# Sheet_X_button.net
KiCad netlist of a schematic drawn in Altium Designer
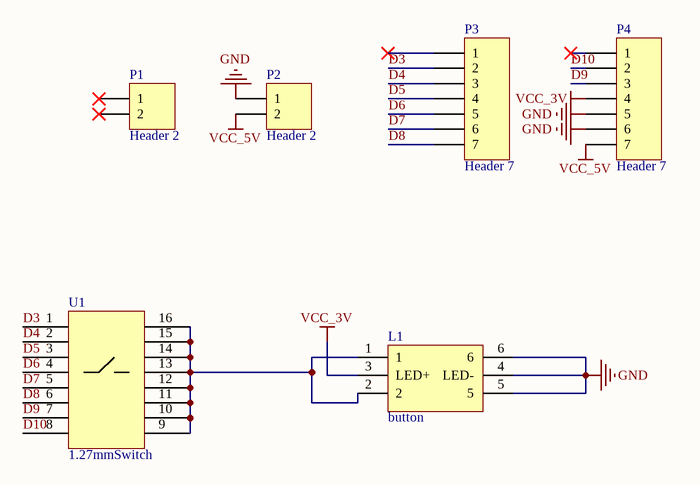
[diagram p0: Sheet_X_button.SchDoc]

(export (version "E")
  (design (tool "Eeschema 10.0.6"))
  (components
    (comp (ref "L1")
      (value "button")
      (footprint "ledbutton")
      (description "蓝色LED按键")
      (libsource (lib "Schlib_OLEDMCU") (part "LEDbutton"))
    )
    (comp (ref "P1")
      (value "Header 2")
      (footprint "HDR1X2")
      (description "Header, 2-Pin")
      (fields (field (name "PUBLISHER") "Altium Limited"))
      (libsource (lib "Miscellaneous Connectors") (part "Header 2"))
    )
    (comp (ref "P2")
      (value "Header 2")
      (footprint "HDR1X2")
      (description "Header, 2-Pin")
      (fields (field (name "PUBLISHER") "Altium Limited"))
      (libsource (lib "Miscellaneous Connectors") (part "Header 2"))
    )
    (comp (ref "P3")
      (value "Header 7")
      (footprint "HDR1X7")
      (description "Header, 7-Pin")
      (fields (field (name "PUBLISHER") "Altium Limited"))
      (libsource (lib "Miscellaneous Connectors") (part "Header 7"))
    )
    (comp (ref "P4")
      (value "Header 7")
      (footprint "HDR1X7")
      (description "Header, 7-Pin")
      (fields (field (name "PUBLISHER") "Altium Limited"))
      (libsource (lib "Miscellaneous Connectors") (part "Header 7"))
    )
    (comp (ref "U1")
      (value "1.27mmSwitch")
      (footprint "NumberSwitch")
      (description "拨码开关")
      (libsource (lib "Schlib_OLEDMCU") (part "NumberSwitch"))
    )
  )
  (nets
    (net (code "1") (name "/D3") (class "Default")
      (node (ref "P3") (pin "2") (pinfunction "2_2") (pintype "passive"))
      (node (ref "U1") (pin "1") (pinfunction "1_1") (pintype "passive"))
    )
    (net (code "2") (name "/D4") (class "Default")
      (node (ref "P3") (pin "3") (pinfunction "3_3") (pintype "passive"))
      (node (ref "U1") (pin "2") (pinfunction "2_2") (pintype "passive"))
    )
    (net (code "3") (name "/D5") (class "Default")
      (node (ref "P3") (pin "4") (pinfunction "4_4") (pintype "passive"))
      (node (ref "U1") (pin "3") (pinfunction "3_3") (pintype "passive"))
    )
    (net (code "4") (name "/D6") (class "Default")
      (node (ref "P3") (pin "5") (pinfunction "5_5") (pintype "passive"))
      (node (ref "U1") (pin "4") (pinfunction "4_4") (pintype "passive"))
    )
    (net (code "5") (name "/D7") (class "Default")
      (node (ref "P3") (pin "6") (pinfunction "6_6") (pintype "passive"))
      (node (ref "U1") (pin "5") (pinfunction "5_5") (pintype "passive"))
    )
    (net (code "6") (name "/D8") (class "Default")
      (node (ref "P3") (pin "7") (pinfunction "7_7") (pintype "passive"))
      (node (ref "U1") (pin "6") (pinfunction "6_6") (pintype "passive"))
    )
    (net (code "7") (name "/D9") (class "Default")
      (node (ref "P4") (pin "3") (pinfunction "3_3") (pintype "passive"))
      (node (ref "U1") (pin "7") (pinfunction "7_7") (pintype "passive"))
    )
    (net (code "8") (name "/D10") (class "Default")
      (node (ref "P4") (pin "2") (pinfunction "2_2") (pintype "passive"))
      (node (ref "U1") (pin "8") (pinfunction "8_8") (pintype "passive"))
    )
    (net (code "9") (name "GND") (class "Default")
      (node (ref "L1") (pin "4") (pinfunction "LED-_4") (pintype "passive"))
      (node (ref "L1") (pin "5") (pinfunction "5_5") (pintype "passive"))
      (node (ref "L1") (pin "6") (pinfunction "6_6") (pintype "passive"))
      (node (ref "P2") (pin "1") (pinfunction "1_1") (pintype "passive"))
      (node (ref "P4") (pin "5") (pinfunction "5_5") (pintype "passive"))
      (node (ref "P4") (pin "6") (pinfunction "6_6") (pintype "passive"))
    )
    (net (code "10") (name "Net-(L1-Pad1)") (class "Default")
      (node (ref "L1") (pin "1") (pinfunction "1_1") (pintype "passive"))
      (node (ref "L1") (pin "2") (pinfunction "2_2") (pintype "passive"))
      (node (ref "U1") (pin "10") (pinfunction "10_10") (pintype "passive"))
      (node (ref "U1") (pin "11") (pinfunction "11_11") (pintype "passive"))
      (node (ref "U1") (pin "12") (pinfunction "12_12") (pintype "passive"))
      (node (ref "U1") (pin "13") (pinfunction "13_13") (pintype "passive"))
      (node (ref "U1") (pin "14") (pinfunction "14_14") (pintype "passive"))
      (node (ref "U1") (pin "15") (pinfunction "15_15") (pintype "passive"))
      (node (ref "U1") (pin "16") (pinfunction "16_16") (pintype "passive"))
      (node (ref "U1") (pin "9") (pinfunction "9_9") (pintype "passive"))
    )
    (net (code "11") (name "VCC_3V") (class "Default")
      (node (ref "L1") (pin "3") (pinfunction "LED+_3") (pintype "passive"))
      (node (ref "P4") (pin "4") (pinfunction "4_4") (pintype "passive"))
    )
    (net (code "12") (name "VCC_5V") (class "Default")
      (node (ref "P2") (pin "2") (pinfunction "2_2") (pintype "passive"))
      (node (ref "P4") (pin "7") (pinfunction "7_7") (pintype "passive"))
    )
    (net (code "13") (name "unconnected-(P1-Pad1)") (class "Default")
      (node (ref "P1") (pin "1") (pinfunction "1_1") (pintype "passive+no_connect"))
    )
    (net (code "14") (name "unconnected-(P1-Pad2)") (class "Default")
      (node (ref "P1") (pin "2") (pinfunction "2_2") (pintype "passive+no_connect"))
    )
    (net (code "15") (name "unconnected-(P3-Pad1)") (class "Default")
      (node (ref "P3") (pin "1") (pinfunction "1_1") (pintype "passive+no_connect"))
    )
    (net (code "16") (name "unconnected-(P4-Pad1)") (class "Default")
      (node (ref "P4") (pin "1") (pinfunction "1_1") (pintype "passive+no_connect"))
    )
  )
)
